# controller.net
KiCad netlist of a schematic drawn in Altium Designer
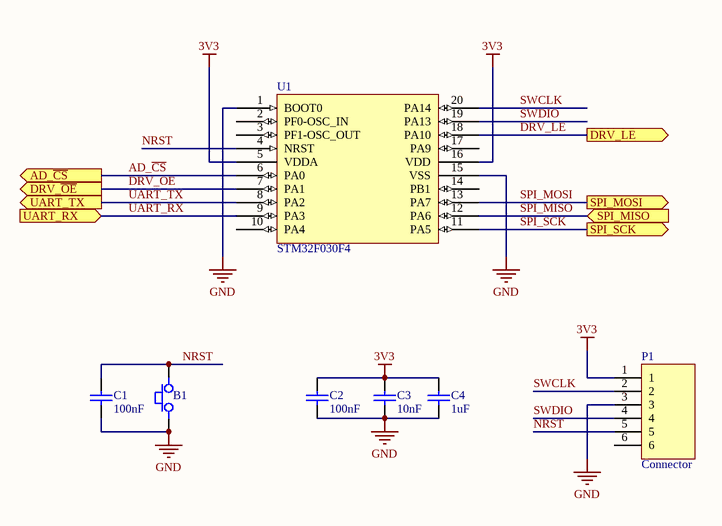
[diagram p0: controller.SchDoc]

(export (version "E")
  (design (tool "Eeschema 10.0.6"))
  (components
    (comp (ref "B1")
      (value "Button")
      (footprint "FP_BTN_SMD_3x6")
      (description "Push button")
      (libsource (lib "hallglib") (part "Button 2P"))
    )
    (comp (ref "C1")
      (value "100nF")
      (footprint "FP_0805_CAP_085")
      (description "Capacitor")
      (libsource (lib "hallglib") (part "CAP"))
    )
    (comp (ref "C2")
      (value "100nF")
      (footprint "FP_0805_CAP_085")
      (description "Capacitor")
      (libsource (lib "hallglib") (part "CAP"))
    )
    (comp (ref "C3")
      (value "10nF")
      (footprint "FP_0805_CAP_085")
      (description "Capacitor")
      (libsource (lib "hallglib") (part "CAP"))
    )
    (comp (ref "C4")
      (value "1uF")
      (footprint "FP_0805_CAP_085")
      (description "Capacitor")
      (libsource (lib "hallglib") (part "CAP"))
    )
    (comp (ref "P1")
      (value "Connector")
      (footprint "FP_CONN6_TAP_254MM")
      (description "6pin connector")
      (libsource (lib "hallglib") (part "Connector_6pin"))
    )
    (comp (ref "U1")
      (value "STM32F030F4")
      (footprint "TSOP65P640X120-20M")
      (libsource (lib "hallglib") (part "STM32F030F4"))
    )
  )
  (nets
    (net (code "1") (name "/AD_~{CS}") (class "Default")
      (node (ref "U1") (pin "6") (pinfunction "PA0_6") (pintype "bidirectional"))
    )
    (net (code "2") (name "/DRV_LE") (class "Default")
      (node (ref "U1") (pin "18") (pinfunction "PA10_18") (pintype "bidirectional"))
    )
    (net (code "3") (name "/DRV_~{OE}") (class "Default")
      (node (ref "U1") (pin "7") (pinfunction "PA1_7") (pintype "bidirectional"))
    )
    (net (code "4") (name "/NRST") (class "Default")
      (node (ref "B1") (pin "2") (pinfunction "2_2") (pintype "passive"))
      (node (ref "C1") (pin "2") (pinfunction "2_2") (pintype "passive"))
      (node (ref "P1") (pin "5") (pinfunction "5_5") (pintype "passive"))
      (node (ref "U1") (pin "4") (pinfunction "NRST_4") (pintype "input"))
    )
    (net (code "5") (name "/SPI_MISO") (class "Default")
      (node (ref "U1") (pin "12") (pinfunction "PA6_12") (pintype "bidirectional"))
    )
    (net (code "6") (name "/SPI_MOSI") (class "Default")
      (node (ref "U1") (pin "13") (pinfunction "PA7_13") (pintype "bidirectional"))
    )
    (net (code "7") (name "/SPI_SCK") (class "Default")
      (node (ref "U1") (pin "11") (pinfunction "PA5_11") (pintype "bidirectional"))
    )
    (net (code "8") (name "/SWCLK") (class "Default")
      (node (ref "P1") (pin "2") (pinfunction "2_2") (pintype "passive"))
      (node (ref "U1") (pin "20") (pinfunction "PA14_20") (pintype "bidirectional"))
    )
    (net (code "9") (name "/SWDIO") (class "Default")
      (node (ref "P1") (pin "4") (pinfunction "4_4") (pintype "passive"))
      (node (ref "U1") (pin "19") (pinfunction "PA13_19") (pintype "bidirectional"))
    )
    (net (code "10") (name "/UART_RX") (class "Default")
      (node (ref "U1") (pin "9") (pinfunction "PA3_9") (pintype "bidirectional"))
    )
    (net (code "11") (name "/UART_TX") (class "Default")
      (node (ref "U1") (pin "8") (pinfunction "PA2_8") (pintype "bidirectional"))
    )
    (net (code "12") (name "3V3") (class "Default")
      (node (ref "C2") (pin "2") (pinfunction "2_2") (pintype "passive"))
      (node (ref "C3") (pin "2") (pinfunction "2_2") (pintype "passive"))
      (node (ref "C4") (pin "2") (pinfunction "2_2") (pintype "passive"))
      (node (ref "P1") (pin "1") (pinfunction "1_1") (pintype "passive"))
      (node (ref "U1") (pin "16") (pinfunction "VDD_16") (pintype "power_in"))
      (node (ref "U1") (pin "5") (pinfunction "VDDA_5") (pintype "power_in"))
    )
    (net (code "13") (name "GND") (class "Default")
      (node (ref "B1") (pin "1") (pinfunction "1_1") (pintype "passive"))
      (node (ref "C1") (pin "1") (pinfunction "1_1") (pintype "passive"))
      (node (ref "C2") (pin "1") (pinfunction "1_1") (pintype "passive"))
      (node (ref "C3") (pin "1") (pinfunction "1_1") (pintype "passive"))
      (node (ref "C4") (pin "1") (pinfunction "1_1") (pintype "passive"))
      (node (ref "P1") (pin "3") (pinfunction "3_3") (pintype "passive"))
      (node (ref "U1") (pin "1") (pinfunction "BOOT0_1") (pintype "input"))
      (node (ref "U1") (pin "15") (pinfunction "VSS_15") (pintype "power_in"))
    )
    (net (code "14") (name "unconnected-(P1-Pad6)") (class "Default")
      (node (ref "P1") (pin "6") (pinfunction "6_6") (pintype "passive"))
    )
    (net (code "15") (name "unconnected-(U1-PA4-Pad10)") (class "Default")
      (node (ref "U1") (pin "10") (pinfunction "PA4_10") (pintype "bidirectional"))
    )
    (net (code "16") (name "unconnected-(U1-PA9-Pad17)") (class "Default")
      (node (ref "U1") (pin "17") (pinfunction "PA9_17") (pintype "bidirectional"))
    )
    (net (code "17") (name "unconnected-(U1-PB1-Pad14)") (class "Default")
      (node (ref "U1") (pin "14") (pinfunction "PB1_14") (pintype "bidirectional"))
    )
    (net (code "18") (name "unconnected-(U1-PF0-OSC_IN-Pad2)") (class "Default")
      (node (ref "U1") (pin "2") (pinfunction "PF0-OSC_IN_2") (pintype "bidirectional"))
    )
    (net (code "19") (name "unconnected-(U1-PF1-OSC_OUT-Pad3)") (class "Default")
      (node (ref "U1") (pin "3") (pinfunction "PF1-OSC_OUT_3") (pintype "bidirectional"))
    )
  )
)
